# klt-kr7-ov7251.net
KiCad netlist of a schematic drawn in Altium Designer
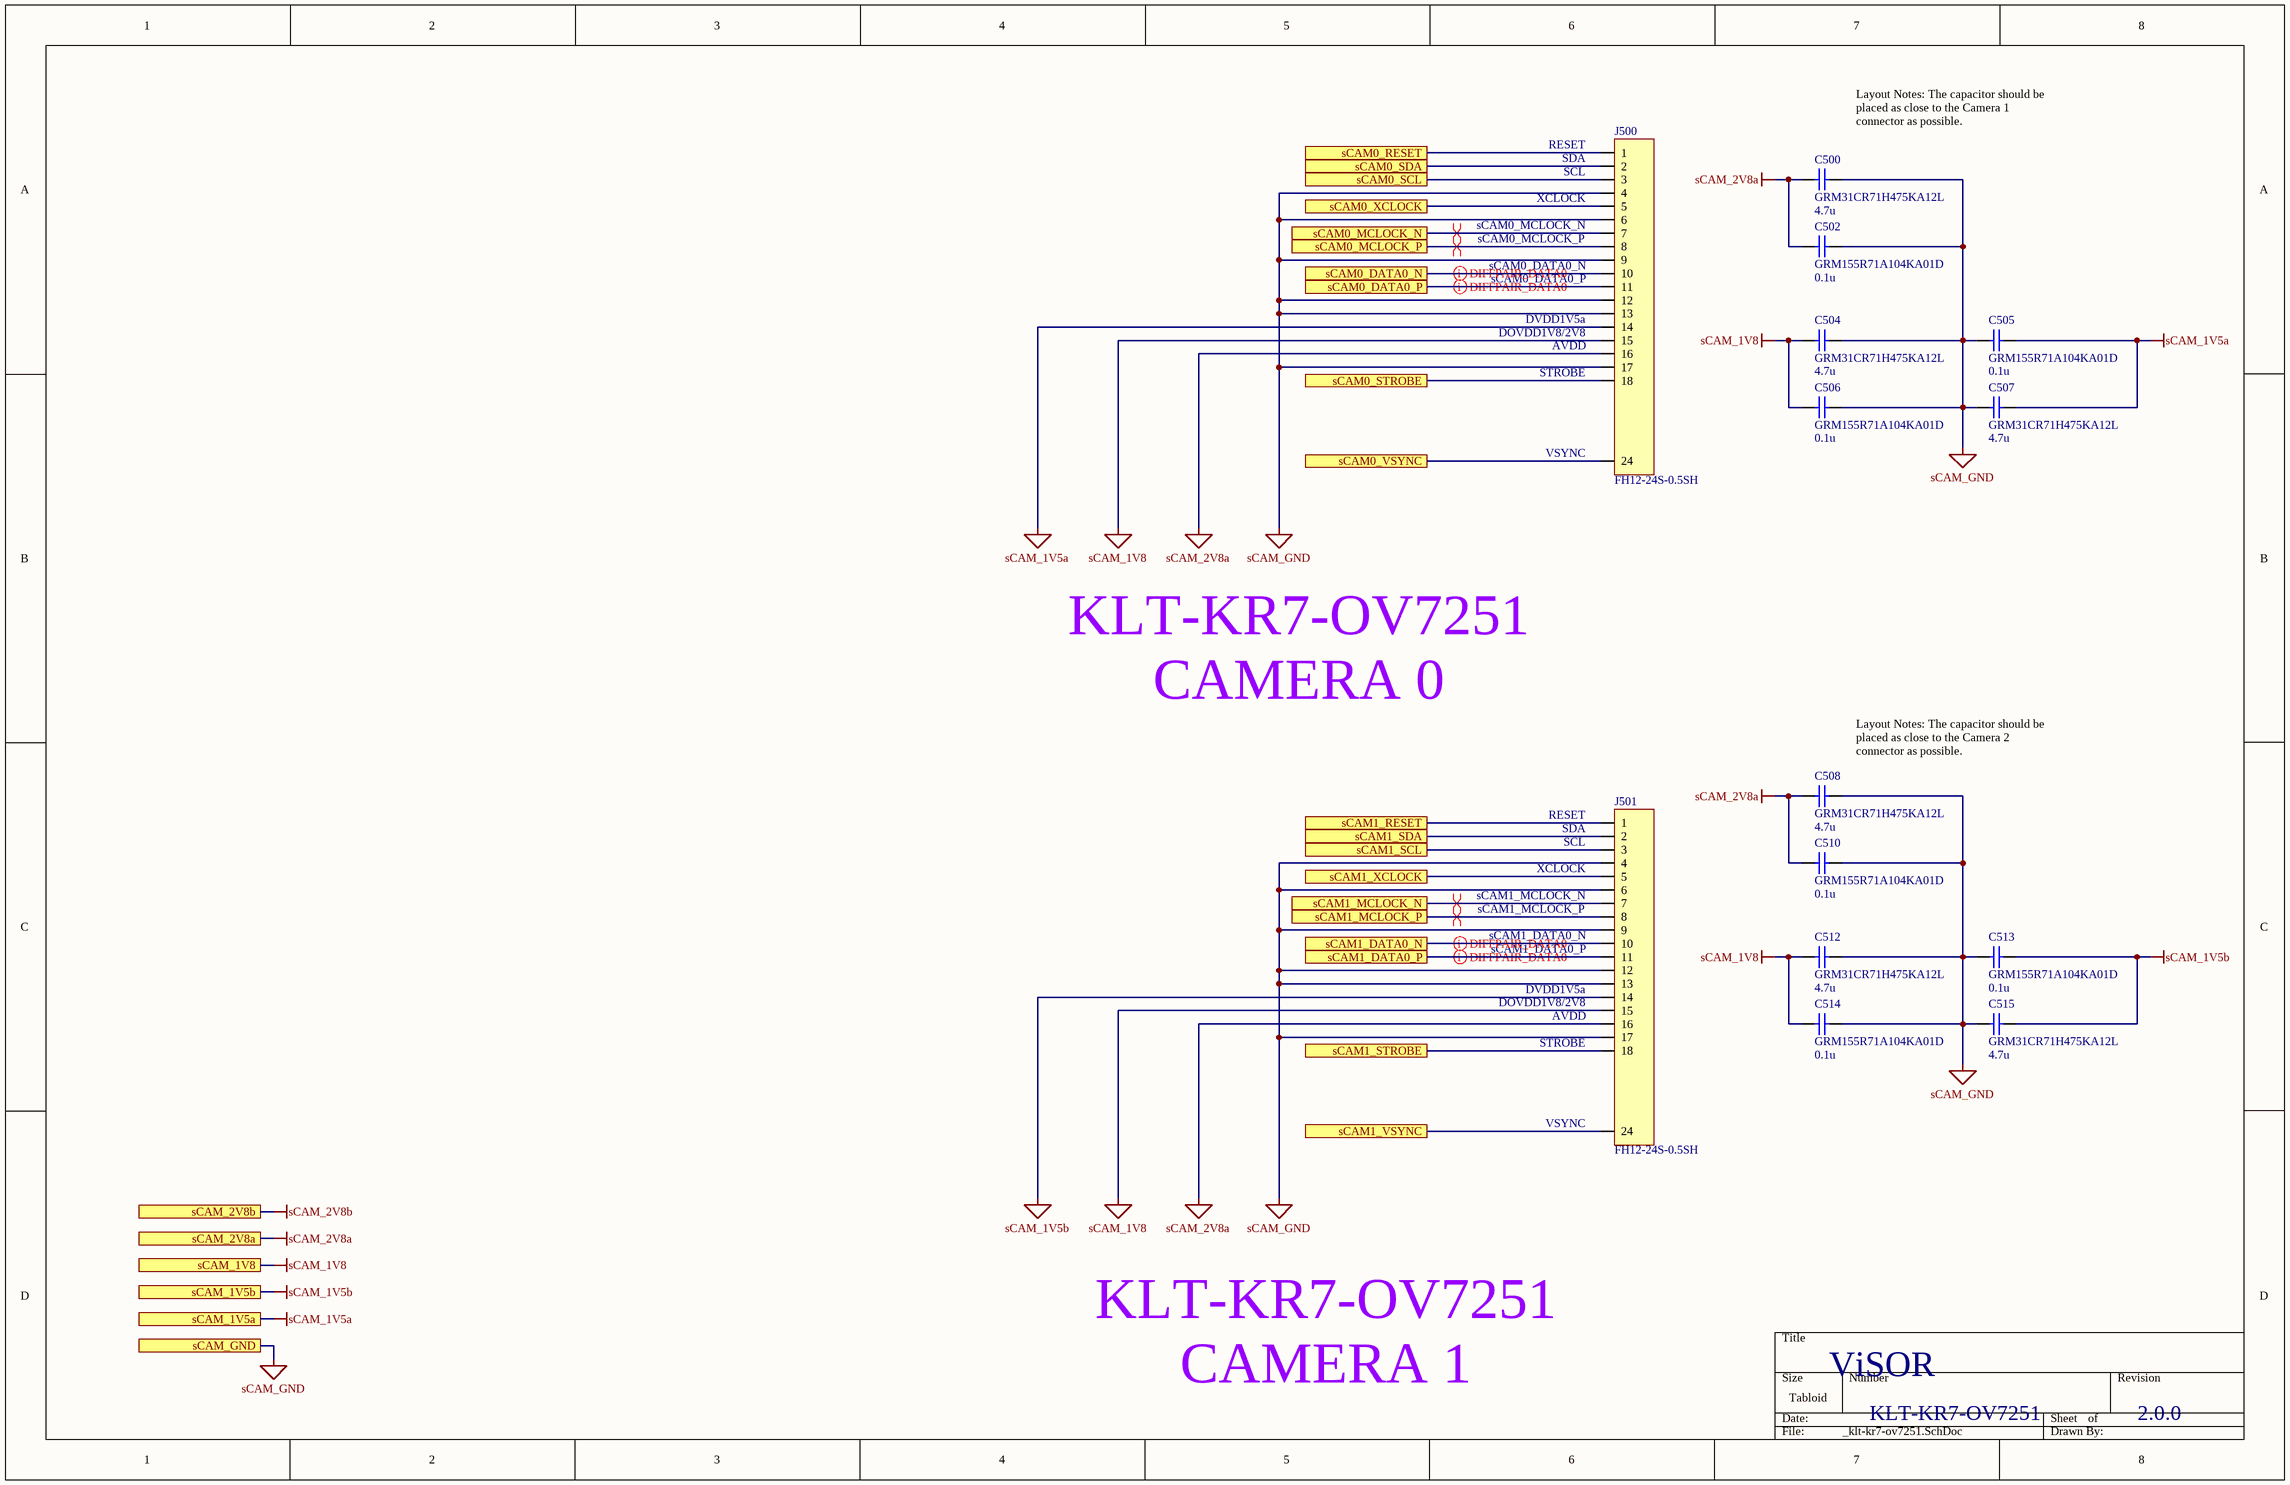
[diagram p0: _klt-kr7-ov7251.SchDoc]

(export (version "E")
  (design (tool "Eeschema 10.0.6"))
  (components
    (comp (ref "C500")
      (value "GRM31CR71H475KA12L")
      (footprint "1206")
      (description "-55-125C, 3216, 50V, X7R, ±10%")
      (fields (field (name "ALTIUM_VALUE") "4.7u"))
      (libsource (lib "standard_capacitors") (part "GRM31CR71HxxxKdddd"))
    )
    (comp (ref "C502")
      (value "GRM155R71A104KA01D")
      (footprint "0402")
      (description "-55-125C, 1005, 10V, X7R, ±10%")
      (fields (field (name "ALTIUM_VALUE") "0.1u"))
      (libsource (lib "standard_capacitors") (part "GRM155R71AxxxKdddd"))
    )
    (comp (ref "C504")
      (value "GRM31CR71H475KA12L")
      (footprint "1206")
      (description "-55-125C, 3216, 50V, X7R, ±10%")
      (fields (field (name "ALTIUM_VALUE") "4.7u"))
      (libsource (lib "standard_capacitors") (part "GRM31CR71HxxxKdddd"))
    )
    (comp (ref "C505")
      (value "GRM155R71A104KA01D")
      (footprint "0402")
      (description "-55-125C, 1005, 10V, X7R, ±10%")
      (fields (field (name "ALTIUM_VALUE") "0.1u"))
      (libsource (lib "standard_capacitors") (part "GRM155R71AxxxKdddd"))
    )
    (comp (ref "C506")
      (value "GRM155R71A104KA01D")
      (footprint "0402")
      (description "-55-125C, 1005, 10V, X7R, ±10%")
      (fields (field (name "ALTIUM_VALUE") "0.1u"))
      (libsource (lib "standard_capacitors") (part "GRM155R71AxxxKdddd"))
    )
    (comp (ref "C507")
      (value "GRM31CR71H475KA12L")
      (footprint "1206")
      (description "-55-125C, 3216, 50V, X7R, ±10%")
      (fields (field (name "ALTIUM_VALUE") "4.7u"))
      (libsource (lib "standard_capacitors") (part "GRM31CR71HxxxKdddd"))
    )
    (comp (ref "C508")
      (value "GRM31CR71H475KA12L")
      (footprint "1206")
      (description "-55-125C, 3216, 50V, X7R, ±10%")
      (fields (field (name "ALTIUM_VALUE") "4.7u"))
      (libsource (lib "standard_capacitors") (part "GRM31CR71HxxxKdddd"))
    )
    (comp (ref "C510")
      (value "GRM155R71A104KA01D")
      (footprint "0402")
      (description "-55-125C, 1005, 10V, X7R, ±10%")
      (fields (field (name "ALTIUM_VALUE") "0.1u"))
      (libsource (lib "standard_capacitors") (part "GRM155R71AxxxKdddd"))
    )
    (comp (ref "C512")
      (value "GRM31CR71H475KA12L")
      (footprint "1206")
      (description "-55-125C, 3216, 50V, X7R, ±10%")
      (fields (field (name "ALTIUM_VALUE") "4.7u"))
      (libsource (lib "standard_capacitors") (part "GRM31CR71HxxxKdddd"))
    )
    (comp (ref "C513")
      (value "GRM155R71A104KA01D")
      (footprint "0402")
      (description "-55-125C, 1005, 10V, X7R, ±10%")
      (fields (field (name "ALTIUM_VALUE") "0.1u"))
      (libsource (lib "standard_capacitors") (part "GRM155R71AxxxKdddd"))
    )
    (comp (ref "C514")
      (value "GRM155R71A104KA01D")
      (footprint "0402")
      (description "-55-125C, 1005, 10V, X7R, ±10%")
      (fields (field (name "ALTIUM_VALUE") "0.1u"))
      (libsource (lib "standard_capacitors") (part "GRM155R71AxxxKdddd"))
    )
    (comp (ref "C515")
      (value "GRM31CR71H475KA12L")
      (footprint "1206")
      (description "-55-125C, 3216, 50V, X7R, ±10%")
      (fields (field (name "ALTIUM_VALUE") "4.7u"))
      (libsource (lib "standard_capacitors") (part "GRM31CR71HxxxKdddd"))
    )
    (comp (ref "J500")
      (value "FH12-24S-0.5SH")
      (footprint "FH12-24S-0.5SH")
      (description "ONN FFC BOTTOM 24POS 0.50MM R/A")
      (libsource (lib "hirose") (part "FH12-24S-0.5SH"))
    )
    (comp (ref "J501")
      (value "FH12-24S-0.5SH")
      (footprint "FH12-24S-0.5SH")
      (description "ONN FFC BOTTOM 24POS 0.50MM R/A")
      (libsource (lib "hirose") (part "FH12-24S-0.5SH"))
    )
  )
  (nets
    (net (code "1") (name "/sCAM0_DATA0_N") (class "Default")
      (node (ref "J500") (pin "10") (pinfunction "10_10") (pintype "passive"))
    )
    (net (code "2") (name "/sCAM0_DATA0_P") (class "Default")
      (node (ref "J500") (pin "11") (pinfunction "11_11") (pintype "passive"))
    )
    (net (code "3") (name "/sCAM0_MCLOCK_N") (class "Default")
      (node (ref "J500") (pin "7") (pinfunction "7_7") (pintype "passive"))
    )
    (net (code "4") (name "/sCAM0_MCLOCK_P") (class "Default")
      (node (ref "J500") (pin "8") (pinfunction "8_8") (pintype "passive"))
    )
    (net (code "5") (name "/sCAM0_RESET") (class "Default")
      (node (ref "J500") (pin "1") (pinfunction "1_1") (pintype "passive"))
    )
    (net (code "6") (name "/sCAM0_SCL") (class "Default")
      (node (ref "J500") (pin "3") (pinfunction "3_3") (pintype "passive"))
    )
    (net (code "7") (name "/sCAM0_SDA") (class "Default")
      (node (ref "J500") (pin "2") (pinfunction "2_2") (pintype "passive"))
    )
    (net (code "8") (name "/sCAM0_STROBE") (class "Default")
      (node (ref "J500") (pin "18") (pinfunction "18_18") (pintype "passive"))
    )
    (net (code "9") (name "/sCAM0_VSYNC") (class "Default")
      (node (ref "J500") (pin "24") (pinfunction "24_24") (pintype "passive"))
    )
    (net (code "10") (name "/sCAM0_XCLOCK") (class "Default")
      (node (ref "J500") (pin "5") (pinfunction "5_5") (pintype "passive"))
    )
    (net (code "11") (name "/sCAM1_DATA0_N") (class "Default")
      (node (ref "J501") (pin "10") (pinfunction "10_10") (pintype "passive"))
    )
    (net (code "12") (name "/sCAM1_DATA0_P") (class "Default")
      (node (ref "J501") (pin "11") (pinfunction "11_11") (pintype "passive"))
    )
    (net (code "13") (name "/sCAM1_MCLOCK_N") (class "Default")
      (node (ref "J501") (pin "7") (pinfunction "7_7") (pintype "passive"))
    )
    (net (code "14") (name "/sCAM1_MCLOCK_P") (class "Default")
      (node (ref "J501") (pin "8") (pinfunction "8_8") (pintype "passive"))
    )
    (net (code "15") (name "/sCAM1_RESET") (class "Default")
      (node (ref "J501") (pin "1") (pinfunction "1_1") (pintype "passive"))
    )
    (net (code "16") (name "/sCAM1_SCL") (class "Default")
      (node (ref "J501") (pin "3") (pinfunction "3_3") (pintype "passive"))
    )
    (net (code "17") (name "/sCAM1_SDA") (class "Default")
      (node (ref "J501") (pin "2") (pinfunction "2_2") (pintype "passive"))
    )
    (net (code "18") (name "/sCAM1_STROBE") (class "Default")
      (node (ref "J501") (pin "18") (pinfunction "18_18") (pintype "passive"))
    )
    (net (code "19") (name "/sCAM1_VSYNC") (class "Default")
      (node (ref "J501") (pin "24") (pinfunction "24_24") (pintype "passive"))
    )
    (net (code "20") (name "/sCAM1_XCLOCK") (class "Default")
      (node (ref "J501") (pin "5") (pinfunction "5_5") (pintype "passive"))
    )
    (net (code "21") (name "sCAM_1V5a") (class "Default")
      (node (ref "C505") (pin "2") (pinfunction "2_2") (pintype "passive"))
      (node (ref "C507") (pin "1") (pinfunction "1_1") (pintype "passive"))
      (node (ref "J500") (pin "14") (pinfunction "14_14") (pintype "passive"))
    )
    (net (code "22") (name "sCAM_1V5b") (class "Default")
      (node (ref "C513") (pin "2") (pinfunction "2_2") (pintype "passive"))
      (node (ref "C515") (pin "1") (pinfunction "1_1") (pintype "passive"))
      (node (ref "J501") (pin "14") (pinfunction "14_14") (pintype "passive"))
    )
    (net (code "23") (name "sCAM_1V8") (class "Default")
      (node (ref "C504") (pin "1") (pinfunction "1_1") (pintype "passive"))
      (node (ref "C506") (pin "2") (pinfunction "2_2") (pintype "passive"))
      (node (ref "C512") (pin "1") (pinfunction "1_1") (pintype "passive"))
      (node (ref "C514") (pin "2") (pinfunction "2_2") (pintype "passive"))
      (node (ref "J500") (pin "15") (pinfunction "15_15") (pintype "passive"))
      (node (ref "J501") (pin "15") (pinfunction "15_15") (pintype "passive"))
    )
    (net (code "24") (name "sCAM_2V8a") (class "Default")
      (node (ref "C500") (pin "1") (pinfunction "1_1") (pintype "passive"))
      (node (ref "C502") (pin "2") (pinfunction "2_2") (pintype "passive"))
      (node (ref "C508") (pin "1") (pinfunction "1_1") (pintype "passive"))
      (node (ref "C510") (pin "2") (pinfunction "2_2") (pintype "passive"))
      (node (ref "J500") (pin "16") (pinfunction "16_16") (pintype "passive"))
      (node (ref "J501") (pin "16") (pinfunction "16_16") (pintype "passive"))
    )
    (net (code "26") (name "sCAM_GND") (class "Default")
      (node (ref "C500") (pin "2") (pinfunction "2_2") (pintype "passive"))
      (node (ref "C502") (pin "1") (pinfunction "1_1") (pintype "passive"))
      (node (ref "C504") (pin "2") (pinfunction "2_2") (pintype "passive"))
      (node (ref "C505") (pin "1") (pinfunction "1_1") (pintype "passive"))
      (node (ref "C506") (pin "1") (pinfunction "1_1") (pintype "passive"))
      (node (ref "C507") (pin "2") (pinfunction "2_2") (pintype "passive"))
      (node (ref "C508") (pin "2") (pinfunction "2_2") (pintype "passive"))
      (node (ref "C510") (pin "1") (pinfunction "1_1") (pintype "passive"))
      (node (ref "C512") (pin "2") (pinfunction "2_2") (pintype "passive"))
      (node (ref "C513") (pin "1") (pinfunction "1_1") (pintype "passive"))
      (node (ref "C514") (pin "1") (pinfunction "1_1") (pintype "passive"))
      (node (ref "C515") (pin "2") (pinfunction "2_2") (pintype "passive"))
      (node (ref "J500") (pin "12") (pinfunction "12_12") (pintype "passive"))
      (node (ref "J500") (pin "13") (pinfunction "13_13") (pintype "passive"))
      (node (ref "J500") (pin "17") (pinfunction "17_17") (pintype "passive"))
      (node (ref "J500") (pin "4") (pinfunction "4_4") (pintype "passive"))
      (node (ref "J500") (pin "6") (pinfunction "6_6") (pintype "passive"))
      (node (ref "J500") (pin "9") (pinfunction "9_9") (pintype "passive"))
      (node (ref "J501") (pin "12") (pinfunction "12_12") (pintype "passive"))
      (node (ref "J501") (pin "13") (pinfunction "13_13") (pintype "passive"))
      (node (ref "J501") (pin "17") (pinfunction "17_17") (pintype "passive"))
      (node (ref "J501") (pin "4") (pinfunction "4_4") (pintype "passive"))
      (node (ref "J501") (pin "6") (pinfunction "6_6") (pintype "passive"))
      (node (ref "J501") (pin "9") (pinfunction "9_9") (pintype "passive"))
    )
    (net (code "27") (name "unconnected-(J500-Pad19)") (class "Default")
      (node (ref "J500") (pin "19") (pinfunction "19_19") (pintype "passive"))
    )
    (net (code "28") (name "unconnected-(J500-Pad20)") (class "Default")
      (node (ref "J500") (pin "20") (pinfunction "20_20") (pintype "passive"))
    )
    (net (code "29") (name "unconnected-(J500-Pad21)") (class "Default")
      (node (ref "J500") (pin "21") (pinfunction "21_21") (pintype "passive"))
    )
    (net (code "30") (name "unconnected-(J500-Pad22)") (class "Default")
      (node (ref "J500") (pin "22") (pinfunction "22_22") (pintype "passive"))
    )
    (net (code "31") (name "unconnected-(J500-Pad23)") (class "Default")
      (node (ref "J500") (pin "23") (pinfunction "23_23") (pintype "passive"))
    )
    (net (code "32") (name "unconnected-(J501-Pad19)") (class "Default")
      (node (ref "J501") (pin "19") (pinfunction "19_19") (pintype "passive"))
    )
    (net (code "33") (name "unconnected-(J501-Pad20)") (class "Default")
      (node (ref "J501") (pin "20") (pinfunction "20_20") (pintype "passive"))
    )
    (net (code "34") (name "unconnected-(J501-Pad21)") (class "Default")
      (node (ref "J501") (pin "21") (pinfunction "21_21") (pintype "passive"))
    )
    (net (code "35") (name "unconnected-(J501-Pad22)") (class "Default")
      (node (ref "J501") (pin "22") (pinfunction "22_22") (pintype "passive"))
    )
    (net (code "36") (name "unconnected-(J501-Pad23)") (class "Default")
      (node (ref "J501") (pin "23") (pinfunction "23_23") (pintype "passive"))
    )
  )
)
